# inverter_logic.net
KiCad netlist of a schematic drawn in EAGLE
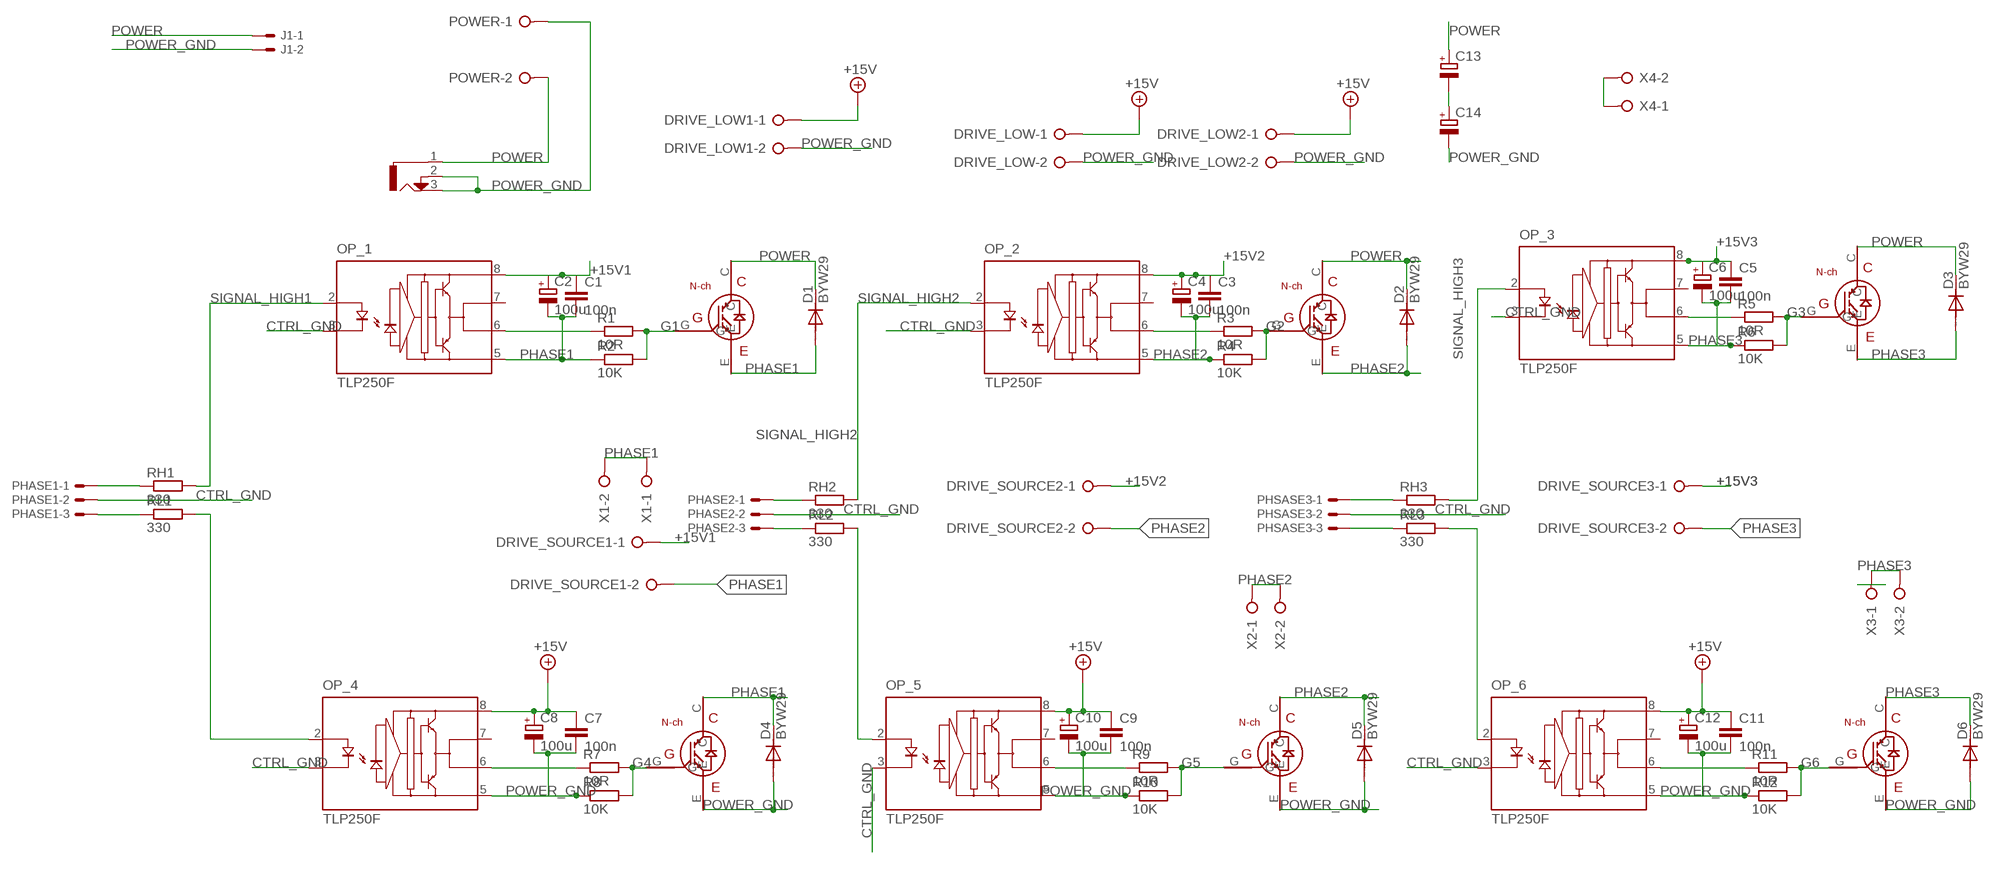
[diagram p0: schematic, sheet 1]

(export (version "E")
  (design (tool "Eeschema 10.0.6"))
  (components
    (comp (ref "C1")
      (value "100n")
      (footprint "eagle-import:C025-025X050")
      (libsource (lib "eagle-import") (part "C-EU025-025X050"))
    )
    (comp (ref "C2")
      (value "100u")
      (footprint "eagle-import:E2,5-6")
      (libsource (lib "eagle-import") (part "CPOL-EUE2.5-6"))
    )
    (comp (ref "C3")
      (value "100n")
      (footprint "eagle-import:C025-025X050")
      (libsource (lib "eagle-import") (part "C-EU025-025X050"))
    )
    (comp (ref "C4")
      (value "100u")
      (footprint "eagle-import:E2,5-6")
      (libsource (lib "eagle-import") (part "CPOL-EUE2.5-6"))
    )
    (comp (ref "C5")
      (value "100n")
      (footprint "eagle-import:C025-025X050")
      (libsource (lib "eagle-import") (part "C-EU025-025X050"))
    )
    (comp (ref "C6")
      (value "100u")
      (footprint "eagle-import:E2,5-6")
      (libsource (lib "eagle-import") (part "CPOL-EUE2.5-6"))
    )
    (comp (ref "C7")
      (value "100n")
      (footprint "eagle-import:C025-025X050")
      (libsource (lib "eagle-import") (part "C-EU025-025X050"))
    )
    (comp (ref "C8")
      (value "100u")
      (footprint "eagle-import:E2,5-6")
      (libsource (lib "eagle-import") (part "CPOL-EUE2.5-6"))
    )
    (comp (ref "C9")
      (value "100n")
      (footprint "eagle-import:C025-025X050")
      (libsource (lib "eagle-import") (part "C-EU025-025X050"))
    )
    (comp (ref "C10")
      (value "100u")
      (footprint "eagle-import:E2,5-6")
      (libsource (lib "eagle-import") (part "CPOL-EUE2.5-6"))
    )
    (comp (ref "C11")
      (value "100n")
      (footprint "eagle-import:C025-025X050")
      (libsource (lib "eagle-import") (part "C-EU025-025X050"))
    )
    (comp (ref "C12")
      (value "100u")
      (footprint "eagle-import:E2,5-6")
      (libsource (lib "eagle-import") (part "CPOL-EUE2.5-6"))
    )
    (comp (ref "C13")
      (value "CPOL-EUE2.5-6")
      (footprint "eagle-import:E2,5-6")
      (libsource (lib "eagle-import") (part "CPOL-EUE2.5-6"))
    )
    (comp (ref "C14")
      (value "CPOL-EUE2.5-6")
      (footprint "eagle-import:E2,5-6")
      (libsource (lib "eagle-import") (part "CPOL-EUE2.5-6"))
    )
    (comp (ref "D1")
      (value "BYW29")
      (footprint "eagle-import:DO220S")
      (libsource (lib "eagle-import") (part "BYW29"))
    )
    (comp (ref "D2")
      (value "BYW29")
      (footprint "eagle-import:DO220S")
      (libsource (lib "eagle-import") (part "BYW29"))
    )
    (comp (ref "D3")
      (value "BYW29")
      (footprint "eagle-import:DO220S")
      (libsource (lib "eagle-import") (part "BYW29"))
    )
    (comp (ref "D4")
      (value "BYW29")
      (footprint "eagle-import:DO220S")
      (libsource (lib "eagle-import") (part "BYW29"))
    )
    (comp (ref "D5")
      (value "BYW29")
      (footprint "eagle-import:DO220S")
      (libsource (lib "eagle-import") (part "BYW29"))
    )
    (comp (ref "D6")
      (value "BYW29")
      (footprint "eagle-import:DO220S")
      (libsource (lib "eagle-import") (part "BYW29"))
    )
    (comp (ref "DRIVE_LOW")
      (value "W237-02P")
      (footprint "eagle-import:W237-132")
      (libsource (lib "eagle-import") (part "W237-02P"))
    )
    (comp (ref "DRIVE_LOW1")
      (value "W237-02P")
      (footprint "eagle-import:W237-132")
      (libsource (lib "eagle-import") (part "W237-02P"))
    )
    (comp (ref "DRIVE_LOW2")
      (value "W237-02P")
      (footprint "eagle-import:W237-132")
      (libsource (lib "eagle-import") (part "W237-02P"))
    )
    (comp (ref "DRIVE_SOURCE1")
      (value "W237-02P")
      (footprint "eagle-import:W237-132")
      (libsource (lib "eagle-import") (part "W237-02P"))
    )
    (comp (ref "DRIVE_SOURCE2")
      (value "W237-02P")
      (footprint "eagle-import:W237-132")
      (libsource (lib "eagle-import") (part "W237-02P"))
    )
    (comp (ref "DRIVE_SOURCE3")
      (value "W237-02P")
      (footprint "eagle-import:W237-132")
      (libsource (lib "eagle-import") (part "W237-02P"))
    )
    (comp (ref "J1")
      (value "22-27-2021-02")
      (footprint "eagle-import:6410-02")
      (libsource (lib "eagle-import") (part "22-?-0227-2021"))
    )
    (comp (ref "OP_1")
      (value "TLP250F")
      (footprint "eagle-import:DIL08")
      (libsource (lib "eagle-import") (part "TLP250F"))
    )
    (comp (ref "OP_2")
      (value "TLP250F")
      (footprint "eagle-import:DIL08")
      (libsource (lib "eagle-import") (part "TLP250F"))
    )
    (comp (ref "OP_3")
      (value "TLP250F")
      (footprint "eagle-import:DIL08")
      (libsource (lib "eagle-import") (part "TLP250F"))
    )
    (comp (ref "OP_4")
      (value "TLP250F")
      (footprint "eagle-import:DIL08")
      (libsource (lib "eagle-import") (part "TLP250F"))
    )
    (comp (ref "OP_5")
      (value "TLP250F")
      (footprint "eagle-import:DIL08")
      (libsource (lib "eagle-import") (part "TLP250F"))
    )
    (comp (ref "OP_6")
      (value "TLP250F")
      (footprint "eagle-import:DIL08")
      (libsource (lib "eagle-import") (part "TLP250F"))
    )
    (comp (ref "PHASE1")
      (value "22-27-2031-03")
      (footprint "eagle-import:6410-03")
      (libsource (lib "eagle-import") (part "22-?-0327-2031"))
    )
    (comp (ref "PHASE2")
      (value "22-27-2031-03")
      (footprint "eagle-import:6410-03")
      (libsource (lib "eagle-import") (part "22-?-0327-2031"))
    )
    (comp (ref "PHSASE3")
      (value "22-27-2031-03")
      (footprint "eagle-import:6410-03")
      (libsource (lib "eagle-import") (part "22-?-0327-2031"))
    )
    (comp (ref "POWER")
      (value "W237-02P")
      (footprint "eagle-import:W237-132")
      (libsource (lib "eagle-import") (part "W237-02P"))
    )
    (comp (ref "R1")
      (value "10R")
      (footprint "eagle-import:0207_10")
      (libsource (lib "eagle-import") (part "R-EU_0207/10"))
    )
    (comp (ref "R2")
      (value "10K")
      (footprint "eagle-import:0207_10")
      (libsource (lib "eagle-import") (part "R-EU_0207/10"))
    )
    (comp (ref "R3")
      (value "10R")
      (footprint "eagle-import:0207_10")
      (libsource (lib "eagle-import") (part "R-EU_0207/10"))
    )
    (comp (ref "R4")
      (value "10K")
      (footprint "eagle-import:0207_10")
      (libsource (lib "eagle-import") (part "R-EU_0207/10"))
    )
    (comp (ref "R5")
      (value "10R")
      (footprint "eagle-import:0207_10")
      (libsource (lib "eagle-import") (part "R-EU_0207/10"))
    )
    (comp (ref "R6")
      (value "10K")
      (footprint "eagle-import:0207_10")
      (libsource (lib "eagle-import") (part "R-EU_0207/10"))
    )
    (comp (ref "R7")
      (value "10R")
      (footprint "eagle-import:0207_10")
      (libsource (lib "eagle-import") (part "R-EU_0207/10"))
    )
    (comp (ref "R8")
      (value "10K")
      (footprint "eagle-import:0207_10")
      (libsource (lib "eagle-import") (part "R-EU_0207/10"))
    )
    (comp (ref "R9")
      (value "10R")
      (footprint "eagle-import:0207_10")
      (libsource (lib "eagle-import") (part "R-EU_0207/10"))
    )
    (comp (ref "R10")
      (value "10K")
      (footprint "eagle-import:0207_10")
      (libsource (lib "eagle-import") (part "R-EU_0207/10"))
    )
    (comp (ref "R11")
      (value "10R")
      (footprint "eagle-import:0207_10")
      (libsource (lib "eagle-import") (part "R-EU_0207/10"))
    )
    (comp (ref "R12")
      (value "10K")
      (footprint "eagle-import:0207_10")
      (libsource (lib "eagle-import") (part "R-EU_0207/10"))
    )
    (comp (ref "RH1")
      (value "330")
      (footprint "eagle-import:0207_10")
      (libsource (lib "eagle-import") (part "R-EU_0207/10"))
    )
    (comp (ref "RH2")
      (value "330")
      (footprint "eagle-import:0207_10")
      (libsource (lib "eagle-import") (part "R-EU_0207/10"))
    )
    (comp (ref "RH3")
      (value "330")
      (footprint "eagle-import:0207_10")
      (libsource (lib "eagle-import") (part "R-EU_0207/10"))
    )
    (comp (ref "RL1")
      (value "330")
      (footprint "eagle-import:0207_10")
      (libsource (lib "eagle-import") (part "R-EU_0207/10"))
    )
    (comp (ref "RL2")
      (value "330")
      (footprint "eagle-import:0207_10")
      (libsource (lib "eagle-import") (part "R-EU_0207/10"))
    )
    (comp (ref "RL3")
      (value "330")
      (footprint "eagle-import:0207_10")
      (libsource (lib "eagle-import") (part "R-EU_0207/10"))
    )
    (comp (ref "T1")
      (value "TO-247A")
      (footprint "eagle-import:TO-247")
      (libsource (lib "eagle-import") (part "TO-247A"))
    )
    (comp (ref "T2")
      (value "TO-247A")
      (footprint "eagle-import:TO-247")
      (libsource (lib "eagle-import") (part "TO-247A"))
    )
    (comp (ref "T3")
      (value "TO-247A")
      (footprint "eagle-import:TO-247")
      (libsource (lib "eagle-import") (part "TO-247A"))
    )
    (comp (ref "T4")
      (value "TO-247A")
      (footprint "eagle-import:TO-247")
      (libsource (lib "eagle-import") (part "TO-247A"))
    )
    (comp (ref "T5")
      (value "TO-247A")
      (footprint "eagle-import:TO-247")
      (libsource (lib "eagle-import") (part "TO-247A"))
    )
    (comp (ref "T6")
      (value "TO-247A")
      (footprint "eagle-import:TO-247")
      (libsource (lib "eagle-import") (part "TO-247A"))
    )
    (comp (ref "U$1")
      (value "DC-21MM")
      (footprint "eagle-import:DC-21MM")
      (libsource (lib "eagle-import") (part "DC-21MM"))
    )
    (comp (ref "X1")
      (value "W237-02P")
      (footprint "eagle-import:W237-132")
      (libsource (lib "eagle-import") (part "W237-02P"))
    )
    (comp (ref "X2")
      (value "W237-02P")
      (footprint "eagle-import:W237-132")
      (libsource (lib "eagle-import") (part "W237-02P"))
    )
    (comp (ref "X3")
      (value "W237-02P")
      (footprint "eagle-import:W237-132")
      (libsource (lib "eagle-import") (part "W237-02P"))
    )
    (comp (ref "X4")
      (value "W237-02P")
      (footprint "eagle-import:W237-132")
      (libsource (lib "eagle-import") (part "W237-02P"))
    )
  )
  (nets
    (net (code "1") (name "+15V") (class "Default")
      (node (ref "C10") (pin "+") (pinfunction "+_+") (pintype "passive"))
      (node (ref "C11") (pin "1") (pinfunction "1_1") (pintype "passive"))
      (node (ref "C12") (pin "+") (pinfunction "+_+") (pintype "passive"))
      (node (ref "C7") (pin "1") (pinfunction "1_1") (pintype "passive"))
      (node (ref "C8") (pin "+") (pinfunction "+_+") (pintype "passive"))
      (node (ref "C9") (pin "1") (pinfunction "1_1") (pintype "passive"))
      (node (ref "DRIVE_LOW") (pin "1") (pinfunction "KL_1") (pintype "passive"))
      (node (ref "DRIVE_LOW1") (pin "1") (pinfunction "KL_1") (pintype "passive"))
      (node (ref "DRIVE_LOW2") (pin "1") (pinfunction "KL_1") (pintype "passive"))
      (node (ref "OP_4") (pin "8") (pinfunction "VCC_8") (pintype "bidirectional"))
      (node (ref "OP_5") (pin "8") (pinfunction "VCC_8") (pintype "bidirectional"))
      (node (ref "OP_6") (pin "8") (pinfunction "VCC_8") (pintype "bidirectional"))
    )
    (net (code "2") (name "/+15V1") (class "Default")
      (node (ref "C1") (pin "1") (pinfunction "1_1") (pintype "passive"))
      (node (ref "C2") (pin "+") (pinfunction "+_+") (pintype "passive"))
      (node (ref "DRIVE_SOURCE1") (pin "1") (pinfunction "KL_1") (pintype "passive"))
      (node (ref "OP_1") (pin "8") (pinfunction "VCC_8") (pintype "bidirectional"))
    )
    (net (code "3") (name "/+15V2") (class "Default")
      (node (ref "C3") (pin "1") (pinfunction "1_1") (pintype "passive"))
      (node (ref "C4") (pin "+") (pinfunction "+_+") (pintype "passive"))
      (node (ref "DRIVE_SOURCE2") (pin "1") (pinfunction "KL_1") (pintype "passive"))
      (node (ref "OP_2") (pin "8") (pinfunction "VCC_8") (pintype "bidirectional"))
    )
    (net (code "4") (name "/+15V3") (class "Default")
      (node (ref "C5") (pin "1") (pinfunction "1_1") (pintype "passive"))
      (node (ref "C6") (pin "+") (pinfunction "+_+") (pintype "passive"))
      (node (ref "DRIVE_SOURCE3") (pin "1") (pinfunction "KL_1") (pintype "passive"))
      (node (ref "OP_3") (pin "8") (pinfunction "VCC_8") (pintype "bidirectional"))
    )
    (net (code "5") (name "/CTRL_GND") (class "Default")
      (node (ref "OP_1") (pin "3") (pinfunction "K_3") (pintype "bidirectional"))
      (node (ref "OP_2") (pin "3") (pinfunction "K_3") (pintype "bidirectional"))
      (node (ref "OP_3") (pin "3") (pinfunction "K_3") (pintype "bidirectional"))
      (node (ref "OP_4") (pin "3") (pinfunction "K_3") (pintype "bidirectional"))
      (node (ref "OP_5") (pin "3") (pinfunction "K_3") (pintype "bidirectional"))
      (node (ref "OP_6") (pin "3") (pinfunction "K_3") (pintype "bidirectional"))
      (node (ref "PHASE1") (pin "2") (pinfunction "S_2") (pintype "passive"))
      (node (ref "PHASE2") (pin "2") (pinfunction "S_2") (pintype "passive"))
      (node (ref "PHSASE3") (pin "2") (pinfunction "S_2") (pintype "passive"))
    )
    (net (code "6") (name "/G1") (class "Default")
      (node (ref "R1") (pin "2") (pinfunction "2_2") (pintype "passive"))
      (node (ref "R2") (pin "2") (pinfunction "2_2") (pintype "passive"))
      (node (ref "T1") (pin "G") (pinfunction "G_G") (pintype "bidirectional"))
    )
    (net (code "7") (name "/G2") (class "Default")
      (node (ref "R3") (pin "2") (pinfunction "2_2") (pintype "passive"))
      (node (ref "R4") (pin "2") (pinfunction "2_2") (pintype "passive"))
      (node (ref "T2") (pin "G") (pinfunction "G_G") (pintype "bidirectional"))
    )
    (net (code "8") (name "/G3") (class "Default")
      (node (ref "R5") (pin "2") (pinfunction "2_2") (pintype "passive"))
      (node (ref "R6") (pin "2") (pinfunction "2_2") (pintype "passive"))
      (node (ref "T3") (pin "G") (pinfunction "G_G") (pintype "bidirectional"))
    )
    (net (code "9") (name "/G4") (class "Default")
      (node (ref "R7") (pin "2") (pinfunction "2_2") (pintype "passive"))
      (node (ref "R8") (pin "2") (pinfunction "2_2") (pintype "passive"))
      (node (ref "T4") (pin "G") (pinfunction "G_G") (pintype "bidirectional"))
    )
    (net (code "10") (name "/G5") (class "Default")
      (node (ref "R10") (pin "2") (pinfunction "2_2") (pintype "passive"))
      (node (ref "R9") (pin "2") (pinfunction "2_2") (pintype "passive"))
      (node (ref "T5") (pin "G") (pinfunction "G_G") (pintype "bidirectional"))
    )
    (net (code "11") (name "/G6") (class "Default")
      (node (ref "R11") (pin "2") (pinfunction "2_2") (pintype "passive"))
      (node (ref "R12") (pin "2") (pinfunction "2_2") (pintype "passive"))
      (node (ref "T6") (pin "G") (pinfunction "G_G") (pintype "bidirectional"))
    )
    (net (code "12") (name "/N") (class "Default")
      (node (ref "C13") (pin "-") (pinfunction "-_-") (pintype "passive"))
      (node (ref "C14") (pin "+") (pinfunction "+_+") (pintype "passive"))
      (node (ref "X4") (pin "1") (pinfunction "KL_1") (pintype "passive"))
      (node (ref "X4") (pin "2") (pinfunction "KL_2") (pintype "passive"))
    )
    (net (code "13") (name "/POWER") (class "Default")
      (node (ref "C13") (pin "+") (pinfunction "+_+") (pintype "passive"))
      (node (ref "D1") (pin "C") (pinfunction "C_C") (pintype "passive"))
      (node (ref "D2") (pin "C") (pinfunction "C_C") (pintype "passive"))
      (node (ref "D3") (pin "C") (pinfunction "C_C") (pintype "passive"))
      (node (ref "J1") (pin "1") (pinfunction "S_1") (pintype "passive"))
      (node (ref "POWER") (pin "2") (pinfunction "KL_2") (pintype "passive"))
      (node (ref "T1") (pin "C") (pinfunction "C_C") (pintype "bidirectional"))
      (node (ref "T2") (pin "C") (pinfunction "C_C") (pintype "bidirectional"))
      (node (ref "T3") (pin "C") (pinfunction "C_C") (pintype "bidirectional"))
      (node (ref "U$1") (pin "1") (pinfunction "1_1") (pintype "passive"))
    )
    (net (code "14") (name "/POWER_GND") (class "Default")
      (node (ref "C10") (pin "-") (pinfunction "-_-") (pintype "passive"))
      (node (ref "C11") (pin "2") (pinfunction "2_2") (pintype "passive"))
      (node (ref "C12") (pin "-") (pinfunction "-_-") (pintype "passive"))
      (node (ref "C14") (pin "-") (pinfunction "-_-") (pintype "passive"))
      (node (ref "C7") (pin "2") (pinfunction "2_2") (pintype "passive"))
      (node (ref "C8") (pin "-") (pinfunction "-_-") (pintype "passive"))
      (node (ref "C9") (pin "2") (pinfunction "2_2") (pintype "passive"))
      (node (ref "D4") (pin "A") (pinfunction "A_A") (pintype "passive"))
      (node (ref "D5") (pin "A") (pinfunction "A_A") (pintype "passive"))
      (node (ref "D6") (pin "A") (pinfunction "A_A") (pintype "passive"))
      (node (ref "DRIVE_LOW") (pin "2") (pinfunction "KL_2") (pintype "passive"))
      (node (ref "DRIVE_LOW1") (pin "2") (pinfunction "KL_2") (pintype "passive"))
      (node (ref "DRIVE_LOW2") (pin "2") (pinfunction "KL_2") (pintype "passive"))
      (node (ref "J1") (pin "2") (pinfunction "S_2") (pintype "passive"))
      (node (ref "OP_4") (pin "5") (pinfunction "GND_5") (pintype "bidirectional"))
      (node (ref "OP_5") (pin "5") (pinfunction "GND_5") (pintype "bidirectional"))
      (node (ref "OP_6") (pin "5") (pinfunction "GND_5") (pintype "bidirectional"))
      (node (ref "POWER") (pin "1") (pinfunction "KL_1") (pintype "passive"))
      (node (ref "R10") (pin "1") (pinfunction "1_1") (pintype "passive"))
      (node (ref "R12") (pin "1") (pinfunction "1_1") (pintype "passive"))
      (node (ref "R8") (pin "1") (pinfunction "1_1") (pintype "passive"))
      (node (ref "T4") (pin "E") (pinfunction "E_E") (pintype "bidirectional"))
      (node (ref "T5") (pin "E") (pinfunction "E_E") (pintype "bidirectional"))
      (node (ref "T6") (pin "E") (pinfunction "E_E") (pintype "bidirectional"))
      (node (ref "U$1") (pin "2") (pinfunction "2_2") (pintype "passive"))
      (node (ref "U$1") (pin "3") (pinfunction "3_3") (pintype "passive"))
    )
    (net (code "15") (name "/SIGNAL_HIGH1") (class "Default")
      (node (ref "OP_1") (pin "2") (pinfunction "A_2") (pintype "bidirectional"))
      (node (ref "RH1") (pin "2") (pinfunction "2_2") (pintype "passive"))
    )
    (net (code "16") (name "/SIGNAL_HIGH2") (class "Default")
      (node (ref "OP_2") (pin "2") (pinfunction "A_2") (pintype "bidirectional"))
      (node (ref "RH2") (pin "2") (pinfunction "2_2") (pintype "passive"))
    )
    (net (code "17") (name "/SIGNAL_HIGH3") (class "Default")
      (node (ref "OP_3") (pin "2") (pinfunction "A_2") (pintype "bidirectional"))
      (node (ref "RH3") (pin "2") (pinfunction "2_2") (pintype "passive"))
    )
    (net (code "18") (name "Net-(OP_1-VO)") (class "Default")
      (node (ref "OP_1") (pin "6") (pinfunction "VO_6") (pintype "bidirectional"))
      (node (ref "R1") (pin "1") (pinfunction "1_1") (pintype "passive"))
    )
    (net (code "19") (name "Net-(OP_2-VO)") (class "Default")
      (node (ref "OP_2") (pin "6") (pinfunction "VO_6") (pintype "bidirectional"))
      (node (ref "R3") (pin "1") (pinfunction "1_1") (pintype "passive"))
    )
    (net (code "20") (name "Net-(OP_3-VO)") (class "Default")
      (node (ref "OP_3") (pin "6") (pinfunction "VO_6") (pintype "bidirectional"))
      (node (ref "R5") (pin "1") (pinfunction "1_1") (pintype "passive"))
    )
    (net (code "21") (name "Net-(OP_4-A)") (class "Default")
      (node (ref "OP_4") (pin "2") (pinfunction "A_2") (pintype "bidirectional"))
      (node (ref "RL1") (pin "2") (pinfunction "2_2") (pintype "passive"))
    )
    (net (code "22") (name "Net-(OP_4-VO)") (class "Default")
      (node (ref "OP_4") (pin "6") (pinfunction "VO_6") (pintype "bidirectional"))
      (node (ref "R7") (pin "1") (pinfunction "1_1") (pintype "passive"))
    )
    (net (code "23") (name "Net-(OP_5-A)") (class "Default")
      (node (ref "OP_5") (pin "2") (pinfunction "A_2") (pintype "bidirectional"))
      (node (ref "RL2") (pin "2") (pinfunction "2_2") (pintype "passive"))
    )
    (net (code "24") (name "Net-(OP_5-VO)") (class "Default")
      (node (ref "OP_5") (pin "6") (pinfunction "VO_6") (pintype "bidirectional"))
      (node (ref "R9") (pin "1") (pinfunction "1_1") (pintype "passive"))
    )
    (net (code "25") (name "Net-(OP_6-A)") (class "Default")
      (node (ref "OP_6") (pin "2") (pinfunction "A_2") (pintype "bidirectional"))
      (node (ref "RL3") (pin "2") (pinfunction "2_2") (pintype "passive"))
    )
    (net (code "26") (name "Net-(OP_6-VO)") (class "Default")
      (node (ref "OP_6") (pin "6") (pinfunction "VO_6") (pintype "bidirectional"))
      (node (ref "R11") (pin "1") (pinfunction "1_1") (pintype "passive"))
    )
    (net (code "27") (name "Net-(PHASE1A-S)") (class "Default")
      (node (ref "PHASE1") (pin "1") (pinfunction "S_1") (pintype "passive"))
      (node (ref "RH1") (pin "1") (pinfunction "1_1") (pintype "passive"))
    )
    (net (code "28") (name "Net-(PHASE1C-S)") (class "Default")
      (node (ref "PHASE1") (pin "3") (pinfunction "S_3") (pintype "passive"))
      (node (ref "RL1") (pin "1") (pinfunction "1_1") (pintype "passive"))
    )
    (net (code "29") (name "Net-(PHASE2A-S)") (class "Default")
      (node (ref "PHASE2") (pin "1") (pinfunction "S_1") (pintype "passive"))
      (node (ref "RH2") (pin "1") (pinfunction "1_1") (pintype "passive"))
    )
    (net (code "30") (name "Net-(PHASE2C-S)") (class "Default")
      (node (ref "PHASE2") (pin "3") (pinfunction "S_3") (pintype "passive"))
      (node (ref "RL2") (pin "1") (pinfunction "1_1") (pintype "passive"))
    )
    (net (code "31") (name "Net-(PHSASE3A-S)") (class "Default")
      (node (ref "PHSASE3") (pin "1") (pinfunction "S_1") (pintype "passive"))
      (node (ref "RH3") (pin "1") (pinfunction "1_1") (pintype "passive"))
    )
    (net (code "32") (name "Net-(PHSASE3C-S)") (class "Default")
      (node (ref "PHSASE3") (pin "3") (pinfunction "S_3") (pintype "passive"))
      (node (ref "RL3") (pin "1") (pinfunction "1_1") (pintype "passive"))
    )
    (net (code "33") (name "PHASE1") (class "Default")
      (node (ref "C1") (pin "2") (pinfunction "2_2") (pintype "passive"))
      (node (ref "C2") (pin "-") (pinfunction "-_-") (pintype "passive"))
      (node (ref "D1") (pin "A") (pinfunction "A_A") (pintype "passive"))
      (node (ref "D4") (pin "C") (pinfunction "C_C") (pintype "passive"))
      (node (ref "DRIVE_SOURCE1") (pin "2") (pinfunction "KL_2") (pintype "passive"))
      (node (ref "OP_1") (pin "5") (pinfunction "GND_5") (pintype "bidirectional"))
      (node (ref "R2") (pin "1") (pinfunction "1_1") (pintype "passive"))
      (node (ref "T1") (pin "E") (pinfunction "E_E") (pintype "bidirectional"))
      (node (ref "T4") (pin "C") (pinfunction "C_C") (pintype "bidirectional"))
      (node (ref "X1") (pin "1") (pinfunction "KL_1") (pintype "passive"))
      (node (ref "X1") (pin "2") (pinfunction "KL_2") (pintype "passive"))
    )
    (net (code "34") (name "PHASE2") (class "Default")
      (node (ref "C3") (pin "2") (pinfunction "2_2") (pintype "passive"))
      (node (ref "C4") (pin "-") (pinfunction "-_-") (pintype "passive"))
      (node (ref "D2") (pin "A") (pinfunction "A_A") (pintype "passive"))
      (node (ref "D5") (pin "C") (pinfunction "C_C") (pintype "passive"))
      (node (ref "DRIVE_SOURCE2") (pin "2") (pinfunction "KL_2") (pintype "passive"))
      (node (ref "OP_2") (pin "5") (pinfunction "GND_5") (pintype "bidirectional"))
      (node (ref "R4") (pin "1") (pinfunction "1_1") (pintype "passive"))
      (node (ref "T2") (pin "E") (pinfunction "E_E") (pintype "bidirectional"))
      (node (ref "T5") (pin "C") (pinfunction "C_C") (pintype "bidirectional"))
      (node (ref "X2") (pin "1") (pinfunction "KL_1") (pintype "passive"))
      (node (ref "X2") (pin "2") (pinfunction "KL_2") (pintype "passive"))
    )
    (net (code "35") (name "PHASE3") (class "Default")
      (node (ref "C5") (pin "2") (pinfunction "2_2") (pintype "passive"))
      (node (ref "C6") (pin "-") (pinfunction "-_-") (pintype "passive"))
      (node (ref "D3") (pin "A") (pinfunction "A_A") (pintype "passive"))
      (node (ref "D6") (pin "C") (pinfunction "C_C") (pintype "passive"))
      (node (ref "DRIVE_SOURCE3") (pin "2") (pinfunction "KL_2") (pintype "passive"))
      (node (ref "OP_3") (pin "5") (pinfunction "GND_5") (pintype "bidirectional"))
      (node (ref "R6") (pin "1") (pinfunction "1_1") (pintype "passive"))
      (node (ref "T3") (pin "E") (pinfunction "E_E") (pintype "bidirectional"))
      (node (ref "T6") (pin "C") (pinfunction "C_C") (pintype "bidirectional"))
      (node (ref "X3") (pin "1") (pinfunction "KL_1") (pintype "passive"))
      (node (ref "X3") (pin "2") (pinfunction "KL_2") (pintype "passive"))
    )
    (net (code "36") (name "unconnected-(OP_1-VO'-Pad7)") (class "Default")
      (node (ref "OP_1") (pin "7") (pinfunction "VO'_7") (pintype "bidirectional"))
    )
    (net (code "37") (name "unconnected-(OP_2-VO'-Pad7)") (class "Default")
      (node (ref "OP_2") (pin "7") (pinfunction "VO'_7") (pintype "bidirectional"))
    )
    (net (code "38") (name "unconnected-(OP_3-VO'-Pad7)") (class "Default")
      (node (ref "OP_3") (pin "7") (pinfunction "VO'_7") (pintype "bidirectional"))
    )
    (net (code "39") (name "unconnected-(OP_4-VO'-Pad7)") (class "Default")
      (node (ref "OP_4") (pin "7") (pinfunction "VO'_7") (pintype "bidirectional"))
    )
    (net (code "40") (name "unconnected-(OP_5-VO'-Pad7)") (class "Default")
      (node (ref "OP_5") (pin "7") (pinfunction "VO'_7") (pintype "bidirectional"))
    )
    (net (code "41") (name "unconnected-(OP_6-VO'-Pad7)") (class "Default")
      (node (ref "OP_6") (pin "7") (pinfunction "VO'_7") (pintype "bidirectional"))
    )
  )
)
